# ATtiny85_Learn2.net
KiCad netlist of a schematic drawn in EAGLE
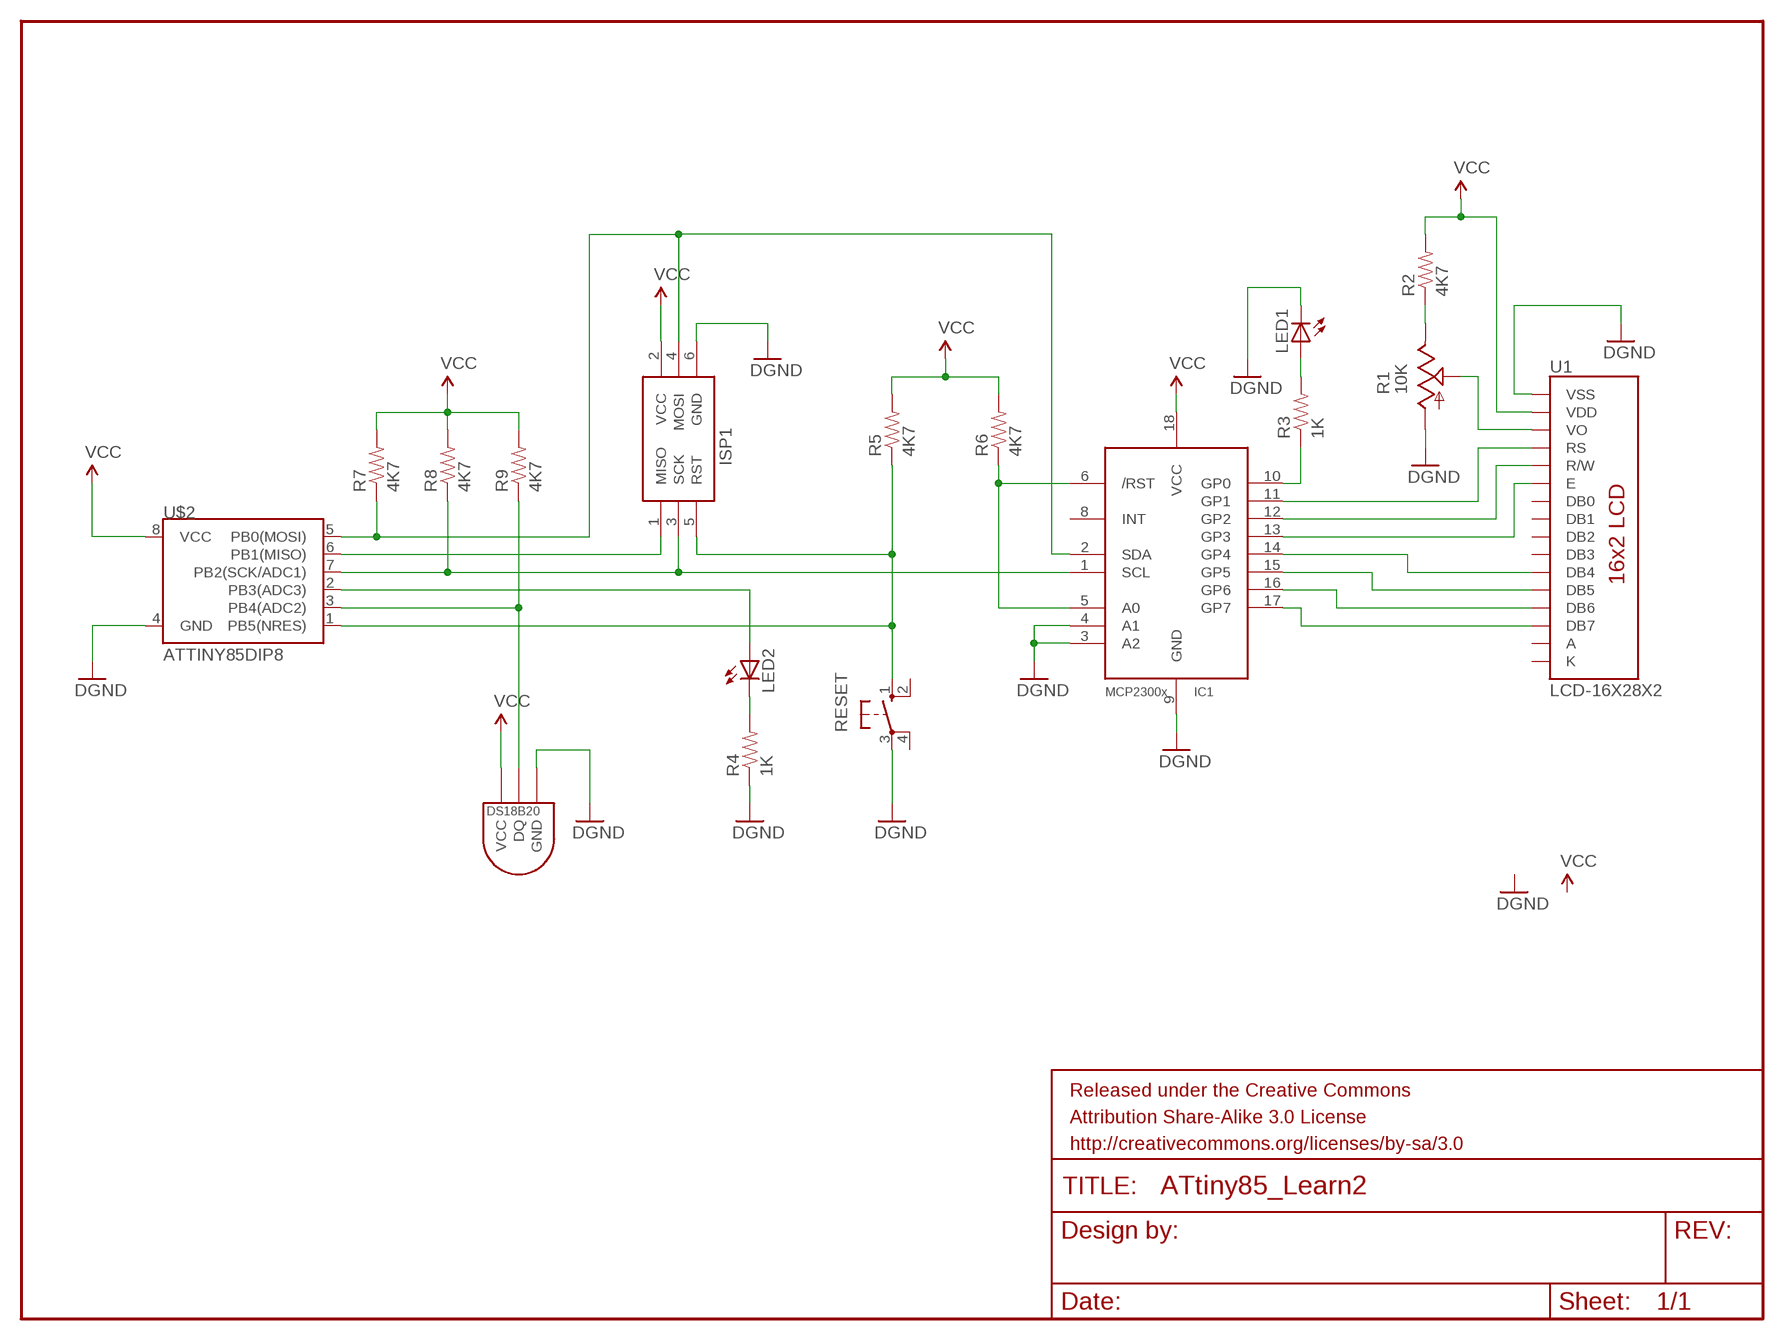
[diagram p0: schematic, sheet 1]

(export (version "E")
  (design (tool "Eeschema 10.0.6"))
  (components
    (comp (ref "IC1")
      (value "MCP2300X/P")
      (footprint "eagle-import:DIL18")
      (libsource (lib "eagle-import") (part "MCP2300X/P"))
    )
    (comp (ref "ISP1")
      (value "AVRISP-6")
      (footprint "eagle-import:AVRISP")
      (libsource (lib "eagle-import") (part "AVRISP-6"))
    )
    (comp (ref "LED1")
      (value "LED5MM")
      (footprint "eagle-import:LED5MM")
      (libsource (lib "eagle-import") (part "LED5MM"))
    )
    (comp (ref "LED2")
      (value "LED5MM")
      (footprint "eagle-import:LED5MM")
      (libsource (lib "eagle-import") (part "LED5MM"))
    )
    (comp (ref "R1")
      (value "10K")
      (footprint "eagle-import:CA6V")
      (libsource (lib "eagle-import") (part "TRIM_US-CA6V"))
    )
    (comp (ref "R2")
      (value "4K7")
      (footprint "eagle-import:AXIAL-0.3")
      (libsource (lib "eagle-import") (part "RESISTORAXIAL-0.3"))
    )
    (comp (ref "R3")
      (value "1K")
      (footprint "eagle-import:AXIAL-0.3")
      (libsource (lib "eagle-import") (part "RESISTORAXIAL-0.3"))
    )
    (comp (ref "R4")
      (value "1K")
      (footprint "eagle-import:AXIAL-0.3")
      (libsource (lib "eagle-import") (part "RESISTORAXIAL-0.3"))
    )
    (comp (ref "R5")
      (value "4K7")
      (footprint "eagle-import:AXIAL-0.3")
      (libsource (lib "eagle-import") (part "RESISTORAXIAL-0.3"))
    )
    (comp (ref "R6")
      (value "4K7")
      (footprint "eagle-import:AXIAL-0.3")
      (libsource (lib "eagle-import") (part "RESISTORAXIAL-0.3"))
    )
    (comp (ref "R7")
      (value "4K7")
      (footprint "eagle-import:AXIAL-0.3")
      (libsource (lib "eagle-import") (part "RESISTORAXIAL-0.3"))
    )
    (comp (ref "R8")
      (value "4K7")
      (footprint "eagle-import:AXIAL-0.3")
      (libsource (lib "eagle-import") (part "RESISTORAXIAL-0.3"))
    )
    (comp (ref "R9")
      (value "4K7")
      (footprint "eagle-import:AXIAL-0.3")
      (libsource (lib "eagle-import") (part "RESISTORAXIAL-0.3"))
    )
    (comp (ref "RESET")
      (value "10-XX")
      (footprint "eagle-import:B3F-10XX")
      (fields (field (name "MPN") "B3F-1000"))
      (libsource (lib "eagle-import") (part "10-XX"))
    )
    (comp (ref "U$1")
      (value "DS1820TO92")
      (footprint "eagle-import:DS1820")
      (libsource (lib "eagle-import") (part "DS1820TO92"))
    )
    (comp (ref "U$2")
      (value "ATTINY85DIP8")
      (footprint "eagle-import:DIP08")
      (libsource (lib "eagle-import") (part "ATTINY45DIP8"))
    )
    (comp (ref "U1")
      (value "LCD-16X28X2")
      (footprint "eagle-import:LCD-8X2")
      (libsource (lib "eagle-import") (part "LCD-16X28X2"))
    )
  )
  (nets
    (net (code "1") (name "/A") (class "Default")
      (node (ref "U1") (pin "15") (pinfunction "A_15") (pintype "power_in"))
    )
    (net (code "2") (name "/K") (class "Default")
      (node (ref "U1") (pin "16") (pinfunction "K_16") (pintype "power_in"))
    )
    (net (code "3") (name "DGND") (class "Default")
      (node (ref "IC1") (pin "3") (pinfunction "A2_3") (pintype "input"))
      (node (ref "IC1") (pin "4") (pinfunction "A1_4") (pintype "input"))
      (node (ref "IC1") (pin "9") (pinfunction "GND_9") (pintype "power_in"))
      (node (ref "ISP1") (pin "6") (pinfunction "GND_6") (pintype "power_in"))
      (node (ref "LED1") (pin "K") (pinfunction "C_K") (pintype "passive"))
      (node (ref "R1") (pin "A") (pinfunction "A_A") (pintype "passive"))
      (node (ref "R4") (pin "P$1") (pinfunction "1_P$1") (pintype "passive"))
      (node (ref "RESET") (pin "3") (pinfunction "P_3") (pintype "passive"))
      (node (ref "U$1") (pin "GND") (pinfunction "GND_GND") (pintype "power_in"))
      (node (ref "U$2") (pin "4") (pinfunction "GND_4") (pintype "bidirectional"))
      (node (ref "U1") (pin "1") (pinfunction "VSS_1") (pintype "power_in"))
    )
    (net (code "4") (name "Net-(IC1-A0)") (class "Default")
      (node (ref "IC1") (pin "5") (pinfunction "A0_5") (pintype "input"))
      (node (ref "IC1") (pin "6") (pinfunction "/RST_6") (pintype "input"))
      (node (ref "R6") (pin "P$1") (pinfunction "1_P$1") (pintype "passive"))
    )
    (net (code "5") (name "Net-(IC1-GP0)") (class "Default")
      (node (ref "IC1") (pin "10") (pinfunction "GP0_10") (pintype "bidirectional"))
      (node (ref "R3") (pin "P$1") (pinfunction "1_P$1") (pintype "passive"))
    )
    (net (code "6") (name "Net-(IC1-GP1)") (class "Default")
      (node (ref "IC1") (pin "11") (pinfunction "GP1_11") (pintype "bidirectional"))
      (node (ref "U1") (pin "4") (pinfunction "RS_4") (pintype "input"))
    )
    (net (code "7") (name "Net-(IC1-GP2)") (class "Default")
      (node (ref "IC1") (pin "12") (pinfunction "GP2_12") (pintype "bidirectional"))
      (node (ref "U1") (pin "5") (pinfunction "R/W_5") (pintype "input"))
    )
    (net (code "8") (name "Net-(IC1-GP3)") (class "Default")
      (node (ref "IC1") (pin "13") (pinfunction "GP3_13") (pintype "bidirectional"))
      (node (ref "U1") (pin "6") (pinfunction "E_6") (pintype "input"))
    )
    (net (code "9") (name "Net-(IC1-GP4)") (class "Default")
      (node (ref "IC1") (pin "14") (pinfunction "GP4_14") (pintype "bidirectional"))
      (node (ref "U1") (pin "11") (pinfunction "DB4_11") (pintype "bidirectional"))
    )
    (net (code "10") (name "Net-(IC1-GP5)") (class "Default")
      (node (ref "IC1") (pin "15") (pinfunction "GP5_15") (pintype "bidirectional"))
      (node (ref "U1") (pin "12") (pinfunction "DB5_12") (pintype "bidirectional"))
    )
    (net (code "11") (name "Net-(IC1-GP6)") (class "Default")
      (node (ref "IC1") (pin "16") (pinfunction "GP6_16") (pintype "bidirectional"))
      (node (ref "U1") (pin "13") (pinfunction "DB6_13") (pintype "bidirectional"))
    )
    (net (code "12") (name "Net-(IC1-GP7)") (class "Default")
      (node (ref "IC1") (pin "17") (pinfunction "GP7_17") (pintype "bidirectional"))
      (node (ref "U1") (pin "14") (pinfunction "DB7_14") (pintype "bidirectional"))
    )
    (net (code "13") (name "Net-(IC1-SCL)") (class "Default")
      (node (ref "IC1") (pin "1") (pinfunction "SCL_1") (pintype "bidirectional"))
      (node (ref "ISP1") (pin "3") (pinfunction "SCK_3") (pintype "output"))
      (node (ref "R8") (pin "P$1") (pinfunction "1_P$1") (pintype "passive"))
      (node (ref "U$2") (pin "7") (pinfunction "PB2(SCK/ADC1)_7") (pintype "bidirectional"))
    )
    (net (code "14") (name "Net-(IC1-SDA)") (class "Default")
      (node (ref "IC1") (pin "2") (pinfunction "SDA_2") (pintype "bidirectional"))
      (node (ref "ISP1") (pin "4") (pinfunction "MOSI_4") (pintype "output"))
      (node (ref "R7") (pin "P$1") (pinfunction "1_P$1") (pintype "passive"))
      (node (ref "U$2") (pin "5") (pinfunction "PB0(MOSI)_5") (pintype "bidirectional"))
    )
    (net (code "15") (name "Net-(ISP1-MISO)") (class "Default")
      (node (ref "ISP1") (pin "1") (pinfunction "MISO_1") (pintype "input"))
      (node (ref "U$2") (pin "6") (pinfunction "PB1(MISO)_6") (pintype "bidirectional"))
    )
    (net (code "16") (name "Net-(ISP1-RST)") (class "Default")
      (node (ref "ISP1") (pin "5") (pinfunction "RST_5") (pintype "output"))
      (node (ref "R5") (pin "P$1") (pinfunction "1_P$1") (pintype "passive"))
      (node (ref "RESET") (pin "1") (pinfunction "S_1") (pintype "passive"))
      (node (ref "U$2") (pin "1") (pinfunction "PB5(NRES)_1") (pintype "bidirectional"))
    )
    (net (code "17") (name "Net-(LED2-C)") (class "Default")
      (node (ref "LED2") (pin "K") (pinfunction "C_K") (pintype "passive"))
      (node (ref "R4") (pin "P$2") (pinfunction "2_P$2") (pintype "passive"))
    )
    (net (code "18") (name "Net-(R2-1)") (class "Default")
      (node (ref "R1") (pin "E") (pinfunction "E_E") (pintype "passive"))
      (node (ref "R2") (pin "P$1") (pinfunction "1_P$1") (pintype "passive"))
    )
    (net (code "19") (name "Net-(R3-2)") (class "Default")
      (node (ref "LED1") (pin "A") (pinfunction "A_A") (pintype "passive"))
      (node (ref "R3") (pin "P$2") (pinfunction "2_P$2") (pintype "passive"))
    )
    (net (code "20") (name "Net-(R9-1)") (class "Default")
      (node (ref "R9") (pin "P$1") (pinfunction "1_P$1") (pintype "passive"))
      (node (ref "U$1") (pin "DQ") (pinfunction "DQ_DQ") (pintype "bidirectional"))
      (node (ref "U$2") (pin "3") (pinfunction "PB4(ADC2)_3") (pintype "bidirectional"))
    )
    (net (code "21") (name "Net-(U$2-PB3(ADC3))") (class "Default")
      (node (ref "LED2") (pin "A") (pinfunction "A_A") (pintype "passive"))
      (node (ref "U$2") (pin "2") (pinfunction "PB3(ADC3)_2") (pintype "bidirectional"))
    )
    (net (code "22") (name "Net-(U1-VO)") (class "Default")
      (node (ref "R1") (pin "S") (pinfunction "S_S") (pintype "passive"))
      (node (ref "U1") (pin "3") (pinfunction "VO_3") (pintype "bidirectional"))
    )
    (net (code "23") (name "VCC") (class "Default")
      (node (ref "IC1") (pin "18") (pinfunction "VCC_18") (pintype "power_in"))
      (node (ref "ISP1") (pin "2") (pinfunction "VCC_2") (pintype "power_in"))
      (node (ref "R2") (pin "P$2") (pinfunction "2_P$2") (pintype "passive"))
      (node (ref "R5") (pin "P$2") (pinfunction "2_P$2") (pintype "passive"))
      (node (ref "R6") (pin "P$2") (pinfunction "2_P$2") (pintype "passive"))
      (node (ref "R7") (pin "P$2") (pinfunction "2_P$2") (pintype "passive"))
      (node (ref "R8") (pin "P$2") (pinfunction "2_P$2") (pintype "passive"))
      (node (ref "R9") (pin "P$2") (pinfunction "2_P$2") (pintype "passive"))
      (node (ref "U$1") (pin "VDD") (pinfunction "VCC_VDD") (pintype "power_in"))
      (node (ref "U$2") (pin "8") (pinfunction "VCC_8") (pintype "bidirectional"))
      (node (ref "U1") (pin "2") (pinfunction "VDD_2") (pintype "power_in"))
    )
    (net (code "24") (name "unconnected-(IC1-INT-Pad8)") (class "Default")
      (node (ref "IC1") (pin "8") (pinfunction "INT_8") (pintype "output"))
    )
    (net (code "25") (name "unconnected-(RESET-P1-Pad4)") (class "Default")
      (node (ref "RESET") (pin "4") (pinfunction "P1_4") (pintype "passive"))
    )
    (net (code "26") (name "unconnected-(RESET-S1-Pad2)") (class "Default")
      (node (ref "RESET") (pin "2") (pinfunction "S1_2") (pintype "passive"))
    )
    (net (code "27") (name "unconnected-(U1-DB0-Pad7)") (class "Default")
      (node (ref "U1") (pin "7") (pinfunction "DB0_7") (pintype "bidirectional"))
    )
    (net (code "28") (name "unconnected-(U1-DB1-Pad8)") (class "Default")
      (node (ref "U1") (pin "8") (pinfunction "DB1_8") (pintype "bidirectional"))
    )
    (net (code "29") (name "unconnected-(U1-DB2-Pad9)") (class "Default")
      (node (ref "U1") (pin "9") (pinfunction "DB2_9") (pintype "bidirectional"))
    )
    (net (code "30") (name "unconnected-(U1-DB3-Pad10)") (class "Default")
      (node (ref "U1") (pin "10") (pinfunction "DB3_10") (pintype "bidirectional"))
    )
  )
)
